# Flip_Flop.net
KiCad netlist of a schematic drawn in EAGLE
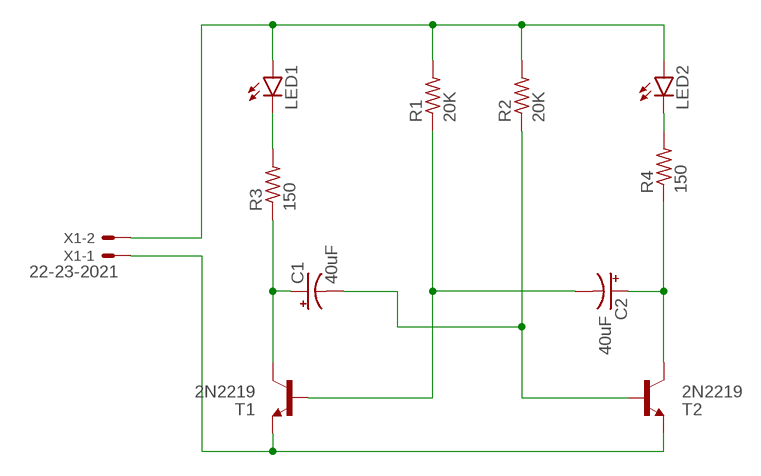
[diagram p0: schematic, sheet 1]

(export (version "E")
  (design (tool "Eeschema 10.0.6"))
  (components
    (comp (ref "C1")
      (value "40uF")
      (footprint "eagle-import:E2,5-6")
      (libsource (lib "eagle-import") (part "CPOL-USE2.5-6"))
    )
    (comp (ref "C2")
      (value "40uF")
      (footprint "eagle-import:E2,5-6")
      (libsource (lib "eagle-import") (part "CPOL-USE2.5-6"))
    )
    (comp (ref "LED1")
      (value "LED5MM")
      (footprint "eagle-import:LED5MM")
      (libsource (lib "eagle-import") (part "LED5MM"))
    )
    (comp (ref "LED2")
      (value "LED5MM")
      (footprint "eagle-import:LED5MM")
      (libsource (lib "eagle-import") (part "LED5MM"))
    )
    (comp (ref "R1")
      (value "20K")
      (footprint "eagle-import:0207_10")
      (libsource (lib "eagle-import") (part "R-US_0207/10"))
    )
    (comp (ref "R2")
      (value "20K")
      (footprint "eagle-import:0207_10")
      (libsource (lib "eagle-import") (part "R-US_0207/10"))
    )
    (comp (ref "R3")
      (value "150")
      (footprint "eagle-import:0207_10")
      (libsource (lib "eagle-import") (part "R-US_0207/10"))
    )
    (comp (ref "R4")
      (value "150")
      (footprint "eagle-import:0207_10")
      (libsource (lib "eagle-import") (part "R-US_0207/10"))
    )
    (comp (ref "T1")
      (value "2N2219")
      (footprint "eagle-import:TO5")
      (libsource (lib "eagle-import") (part "2N2219"))
    )
    (comp (ref "T2")
      (value "2N2219")
      (footprint "eagle-import:TO5")
      (libsource (lib "eagle-import") (part "2N2219"))
    )
    (comp (ref "X1")
      (value "22-23-2021")
      (footprint "eagle-import:22-23-2021")
      (fields (field (name "MF") "MOLEX"))
      (libsource (lib "eagle-import") (part "22-23-2021"))
    )
  )
  (nets
    (net (code "1") (name "Net-(LED1-C)") (class "Default")
      (node (ref "LED1") (pin "K") (pinfunction "C_K") (pintype "passive"))
      (node (ref "R3") (pin "2") (pinfunction "2_2") (pintype "passive"))
    )
    (net (code "2") (name "Net-(LED2-C)") (class "Default")
      (node (ref "LED2") (pin "K") (pinfunction "C_K") (pintype "passive"))
      (node (ref "R4") (pin "2") (pinfunction "2_2") (pintype "passive"))
    )
    (net (code "3") (name "Net-(T1-B)") (class "Default")
      (node (ref "C2") (pin "-") (pinfunction "-_-") (pintype "passive"))
      (node (ref "R1") (pin "1") (pinfunction "1_1") (pintype "passive"))
      (node (ref "T1") (pin "2") (pinfunction "B_2") (pintype "passive"))
    )
    (net (code "4") (name "Net-(T1-C)") (class "Default")
      (node (ref "C1") (pin "+") (pinfunction "+_+") (pintype "passive"))
      (node (ref "R3") (pin "1") (pinfunction "1_1") (pintype "passive"))
      (node (ref "T1") (pin "3") (pinfunction "C_3") (pintype "passive"))
    )
    (net (code "5") (name "Net-(T1-E)") (class "Default")
      (node (ref "T1") (pin "1") (pinfunction "E_1") (pintype "passive"))
      (node (ref "T2") (pin "1") (pinfunction "E_1") (pintype "passive"))
      (node (ref "X1") (pin "1") (pinfunction "S_1") (pintype "passive"))
    )
    (net (code "6") (name "Net-(T2-B)") (class "Default")
      (node (ref "C1") (pin "-") (pinfunction "-_-") (pintype "passive"))
      (node (ref "R2") (pin "1") (pinfunction "1_1") (pintype "passive"))
      (node (ref "T2") (pin "2") (pinfunction "B_2") (pintype "passive"))
    )
    (net (code "7") (name "Net-(T2-C)") (class "Default")
      (node (ref "C2") (pin "+") (pinfunction "+_+") (pintype "passive"))
      (node (ref "R4") (pin "1") (pinfunction "1_1") (pintype "passive"))
      (node (ref "T2") (pin "3") (pinfunction "C_3") (pintype "passive"))
    )
    (net (code "8") (name "Net-(X1B-S)") (class "Default")
      (node (ref "LED1") (pin "A") (pinfunction "A_A") (pintype "passive"))
      (node (ref "LED2") (pin "A") (pinfunction "A_A") (pintype "passive"))
      (node (ref "R1") (pin "2") (pinfunction "2_2") (pintype "passive"))
      (node (ref "R2") (pin "2") (pinfunction "2_2") (pintype "passive"))
      (node (ref "X1") (pin "2") (pinfunction "S_2") (pintype "passive"))
    )
  )
)
